# Inverter_V2.net
KiCad netlist of a schematic drawn in EAGLE
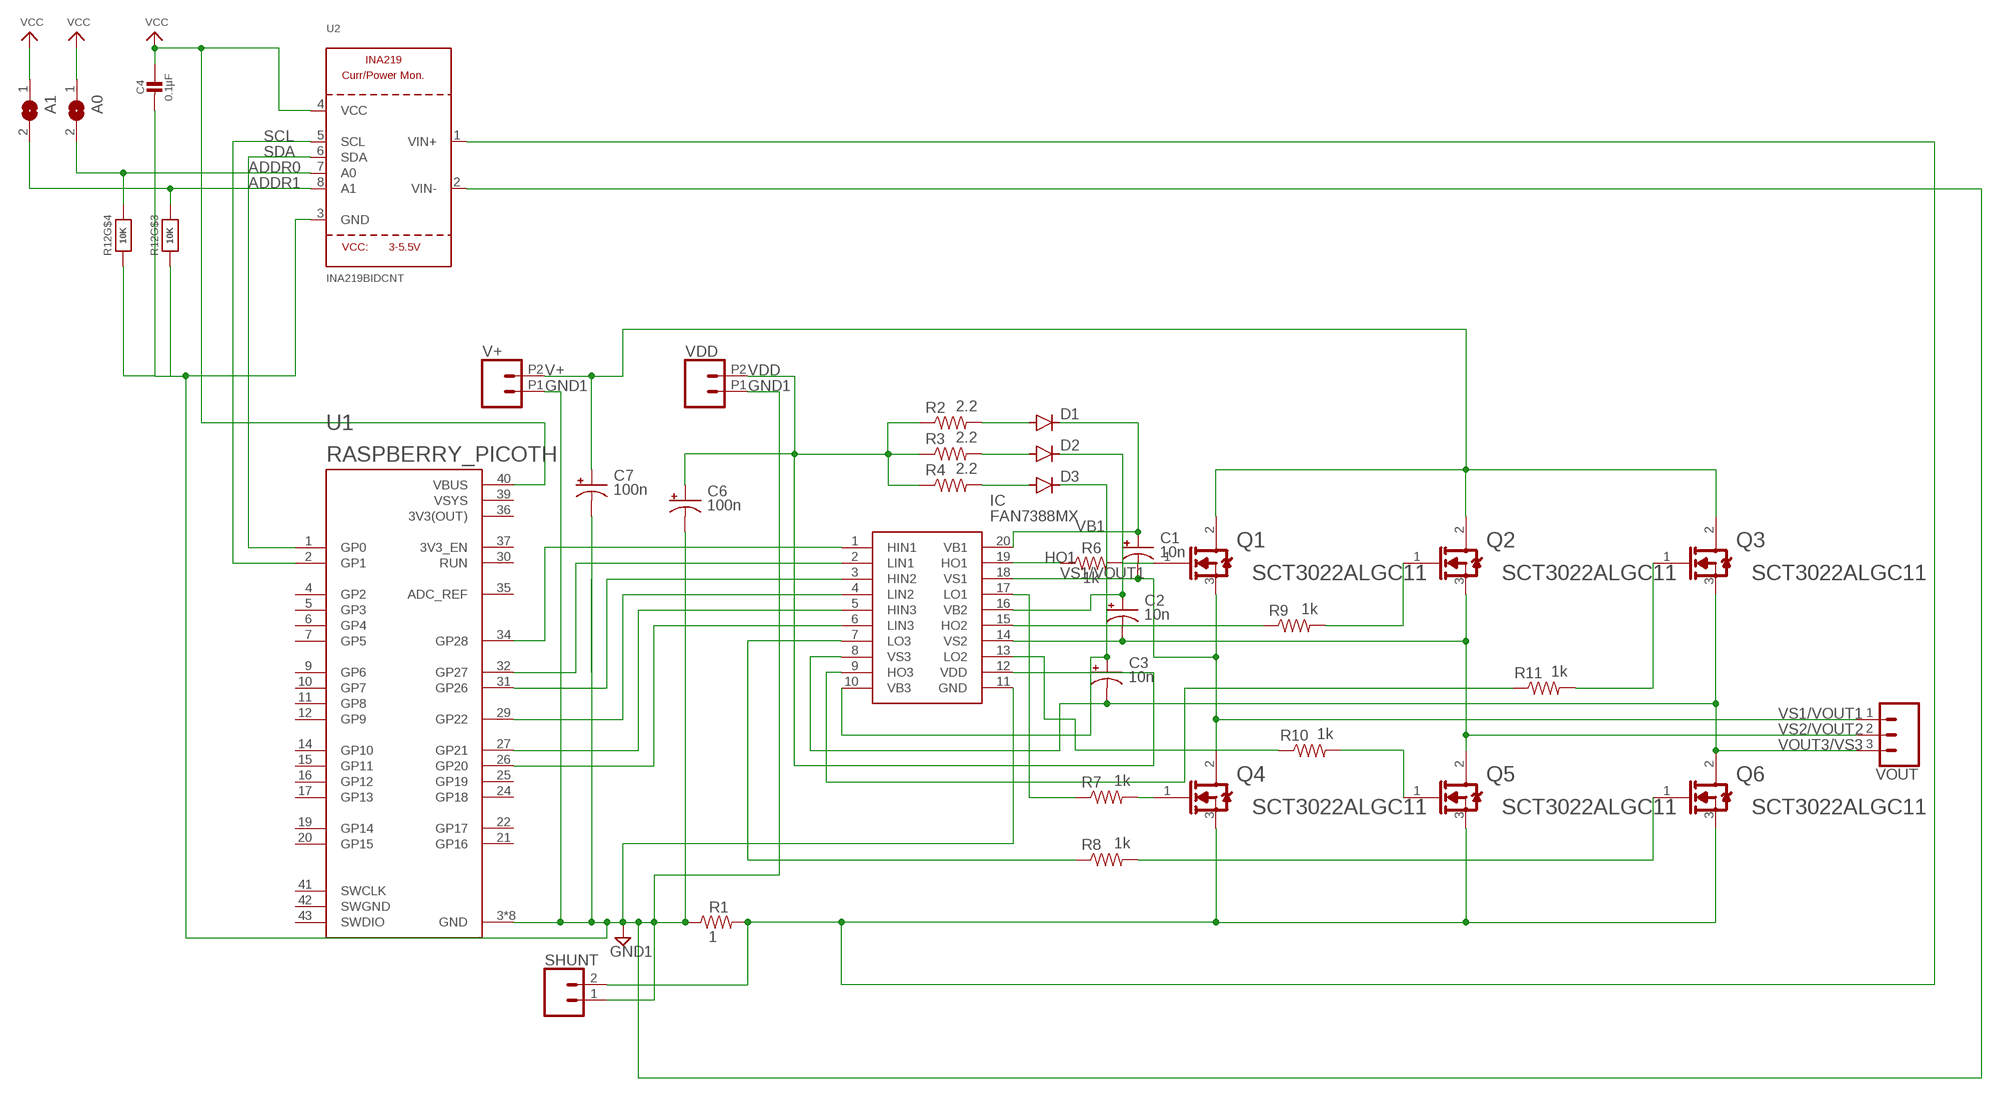
[diagram p0: schematic, sheet 1]

(export (version "E")
  (design (tool "Eeschema 10.0.6"))
  (components
    (comp (ref "A0")
      (value "SOLDERJUMPERREFLOW_NOPASTE")
      (footprint "eagle-import:SOLDERJUMPER_REFLOW_NOPASTE")
      (libsource (lib "eagle-import") (part "SOLDERJUMPERREFLOW_NOPASTE"))
    )
    (comp (ref "A1")
      (value "SOLDERJUMPERREFLOW_NOPASTE")
      (footprint "eagle-import:SOLDERJUMPER_REFLOW_NOPASTE")
      (libsource (lib "eagle-import") (part "SOLDERJUMPERREFLOW_NOPASTE"))
    )
    (comp (ref "C1")
      (value "10n")
      (footprint "eagle-import:SMC_Z")
      (libsource (lib "eagle-import") (part "CPOL-USSMCZ"))
    )
    (comp (ref "C2")
      (value "10n")
      (footprint "eagle-import:SMC_Z")
      (libsource (lib "eagle-import") (part "CPOL-USSMCZ"))
    )
    (comp (ref "C3")
      (value "10n")
      (footprint "eagle-import:SMC_Z")
      (libsource (lib "eagle-import") (part "CPOL-USSMCZ"))
    )
    (comp (ref "C4")
      (value "0.1µF")
      (footprint "eagle-import:0603-NO")
      (libsource (lib "eagle-import") (part "CAP_CERAMIC0603_NO"))
    )
    (comp (ref "C6")
      (value "100n")
      (footprint "eagle-import:SMC_Z")
      (libsource (lib "eagle-import") (part "CPOL-USSMCZ"))
    )
    (comp (ref "C7")
      (value "100n")
      (footprint "eagle-import:E5-5")
      (libsource (lib "eagle-import") (part "CPOL-USE5-5"))
    )
    (comp (ref "D1")
      (value "DIODE-GF1")
      (footprint "eagle-import:GF1")
      (libsource (lib "eagle-import") (part "DIODE-GF1"))
    )
    (comp (ref "D2")
      (value "DIODE-GF1")
      (footprint "eagle-import:GF1")
      (libsource (lib "eagle-import") (part "DIODE-GF1"))
    )
    (comp (ref "D3")
      (value "DIODE-GF1")
      (footprint "eagle-import:GF1")
      (libsource (lib "eagle-import") (part "DIODE-GF1"))
    )
    (comp (ref "IC")
      (value "FAN7388MX")
      (footprint "eagle-import:SOIC127P1032X265-20N")
      (fields (field (name "MOUSER_PART_NUMBER") "512-FAN7388MX"))
      (libsource (lib "eagle-import") (part "FAN7388MX"))
    )
    (comp (ref "Q1")
      (value "ROHM_SCT3022ALGC11ROHM_SCT3022ALGC11_0_0")
      (footprint "eagle-import:ROHM_SCT3022ALGC11_0")
      (fields
        (field (name "DIGIKEY_PART_NUMBER") "SCT3022ALGC11-ND")
        (field (name "MF") "ROHM")
        (field (name "MOUSER_PART_NUMBER") "755-SCT3022ALGC11")
      )
      (libsource (lib "eagle-import") (part "ROHM_SCT3022ALGC11ROHM_SCT3022ALGC11_0_0"))
    )
    (comp (ref "Q2")
      (value "ROHM_SCT3022ALGC11ROHM_SCT3022ALGC11_0_0")
      (footprint "eagle-import:ROHM_SCT3022ALGC11_0")
      (fields
        (field (name "DIGIKEY_PART_NUMBER") "SCT3022ALGC11-ND")
        (field (name "MF") "ROHM")
        (field (name "MOUSER_PART_NUMBER") "755-SCT3022ALGC11")
      )
      (libsource (lib "eagle-import") (part "ROHM_SCT3022ALGC11ROHM_SCT3022ALGC11_0_0"))
    )
    (comp (ref "Q3")
      (value "ROHM_SCT3022ALGC11ROHM_SCT3022ALGC11_0_0")
      (footprint "eagle-import:ROHM_SCT3022ALGC11_0")
      (fields
        (field (name "DIGIKEY_PART_NUMBER") "SCT3022ALGC11-ND")
        (field (name "MF") "ROHM")
        (field (name "MOUSER_PART_NUMBER") "755-SCT3022ALGC11")
      )
      (libsource (lib "eagle-import") (part "ROHM_SCT3022ALGC11ROHM_SCT3022ALGC11_0_0"))
    )
    (comp (ref "Q4")
      (value "ROHM_SCT3022ALGC11ROHM_SCT3022ALGC11_0_0")
      (footprint "eagle-import:ROHM_SCT3022ALGC11_0")
      (fields
        (field (name "DIGIKEY_PART_NUMBER") "SCT3022ALGC11-ND")
        (field (name "MF") "ROHM")
        (field (name "MOUSER_PART_NUMBER") "755-SCT3022ALGC11")
      )
      (libsource (lib "eagle-import") (part "ROHM_SCT3022ALGC11ROHM_SCT3022ALGC11_0_0"))
    )
    (comp (ref "Q5")
      (value "ROHM_SCT3022ALGC11ROHM_SCT3022ALGC11_0_0")
      (footprint "eagle-import:ROHM_SCT3022ALGC11_0")
      (fields
        (field (name "DIGIKEY_PART_NUMBER") "SCT3022ALGC11-ND")
        (field (name "MF") "ROHM")
        (field (name "MOUSER_PART_NUMBER") "755-SCT3022ALGC11")
      )
      (libsource (lib "eagle-import") (part "ROHM_SCT3022ALGC11ROHM_SCT3022ALGC11_0_0"))
    )
    (comp (ref "Q6")
      (value "ROHM_SCT3022ALGC11ROHM_SCT3022ALGC11_0_0")
      (footprint "eagle-import:ROHM_SCT3022ALGC11_0")
      (fields
        (field (name "DIGIKEY_PART_NUMBER") "SCT3022ALGC11-ND")
        (field (name "MF") "ROHM")
        (field (name "MOUSER_PART_NUMBER") "755-SCT3022ALGC11")
      )
      (libsource (lib "eagle-import") (part "ROHM_SCT3022ALGC11ROHM_SCT3022ALGC11_0_0"))
    )
    (comp (ref "R1")
      (value "1")
      (footprint "eagle-import:0207_10")
      (libsource (lib "eagle-import") (part "R-US_0207/10"))
    )
    (comp (ref "R2")
      (value "2.2")
      (footprint "eagle-import:0603")
      (libsource (lib "eagle-import") (part "RESISTOR0603"))
    )
    (comp (ref "R3")
      (value "2.2")
      (footprint "eagle-import:0603")
      (libsource (lib "eagle-import") (part "RESISTOR0603"))
    )
    (comp (ref "R4")
      (value "2.2")
      (footprint "eagle-import:0603")
      (libsource (lib "eagle-import") (part "RESISTOR0603"))
    )
    (comp (ref "R6")
      (value "1k")
      (footprint "eagle-import:0603")
      (libsource (lib "eagle-import") (part "RESISTOR0603"))
    )
    (comp (ref "R7")
      (value "1k")
      (footprint "eagle-import:0603")
      (libsource (lib "eagle-import") (part "RESISTOR0603"))
    )
    (comp (ref "R8")
      (value "1k")
      (footprint "eagle-import:0603")
      (libsource (lib "eagle-import") (part "RESISTOR0603"))
    )
    (comp (ref "R9")
      (value "1k")
      (footprint "eagle-import:0603")
      (libsource (lib "eagle-import") (part "RESISTOR0603"))
    )
    (comp (ref "R10")
      (value "1k")
      (footprint "eagle-import:0603")
      (libsource (lib "eagle-import") (part "RESISTOR0603"))
    )
    (comp (ref "R11")
      (value "1k")
      (footprint "eagle-import:0603")
      (libsource (lib "eagle-import") (part "RESISTOR0603"))
    )
    (comp (ref "R12")
      (value "10K")
      (footprint "eagle-import:RESPACK_4X0603")
      (libsource (lib "eagle-import") (part "RESISTOR_4PACK"))
    )
    (comp (ref "SHUNT")
      (value "CONN_02PTH4")
      (footprint "eagle-import:1X02_XTRA_BIG")
      (libsource (lib "eagle-import") (part "CONN_02PTH4"))
    )
    (comp (ref "U1")
      (value "RASPBERRY_PICOTH")
      (footprint "eagle-import:PICO-PKG-TH")
      (libsource (lib "eagle-import") (part "RASPBERRY_PICOTH"))
    )
    (comp (ref "U2")
      (value "INA219BIDCNT")
      (footprint "eagle-import:SOT23-8")
      (libsource (lib "eagle-import") (part "INA219"))
    )
    (comp (ref "V+")
      (value "CONN_022.54MM_SCREWTERM")
      (footprint "eagle-import:1X02_2.54_SCREWTERM")
      (libsource (lib "eagle-import") (part "CONN_022.54MM_SCREWTERM"))
    )
    (comp (ref "VDD")
      (value "CONN_022.54MM_SCREWTERM")
      (footprint "eagle-import:1X02_2.54_SCREWTERM")
      (libsource (lib "eagle-import") (part "CONN_022.54MM_SCREWTERM"))
    )
    (comp (ref "VOUT")
      (value "CONN_03SCREW-NS")
      (footprint "eagle-import:SCREWTERMINAL-3.5MM-3-NS")
      (libsource (lib "eagle-import") (part "CONN_03SCREW-NS"))
    )
  )
  (nets
    (net (code "1") (name "/3V3(OUT)") (class "Default")
      (node (ref "U1") (pin "36") (pinfunction "3V3(OUT)_36") (pintype "power_in"))
    )
    (net (code "2") (name "/ADDR0") (class "Default")
      (node (ref "A0") (pin "2") (pinfunction "2_2") (pintype "passive"))
      (node (ref "R12") (pin "5") (pinfunction "2_5") (pintype "passive"))
      (node (ref "U2") (pin "7") (pinfunction "A0_7") (pintype "bidirectional"))
    )
    (net (code "3") (name "/ADDR1") (class "Default")
      (node (ref "A1") (pin "2") (pinfunction "2_2") (pintype "passive"))
      (node (ref "R12") (pin "6") (pinfunction "2_6") (pintype "passive"))
      (node (ref "U2") (pin "8") (pinfunction "A1_8") (pintype "bidirectional"))
    )
    (net (code "4") (name "/HO1") (class "Default")
      (node (ref "IC") (pin "19") (pinfunction "HO1_19") (pintype "bidirectional"))
      (node (ref "R6") (pin "1") (pinfunction "1_1") (pintype "passive"))
    )
    (net (code "5") (name "/SCL") (class "Default")
      (node (ref "U1") (pin "2") (pinfunction "GP1_2") (pintype "bidirectional"))
      (node (ref "U2") (pin "5") (pinfunction "SCL_5") (pintype "bidirectional"))
    )
    (net (code "6") (name "/SDA") (class "Default")
      (node (ref "U1") (pin "1") (pinfunction "GP0_1") (pintype "bidirectional"))
      (node (ref "U2") (pin "6") (pinfunction "SDA_6") (pintype "bidirectional"))
    )
    (net (code "7") (name "/SWGND") (class "Default")
      (node (ref "U1") (pin "42") (pinfunction "SWGND_42") (pintype "power_in"))
    )
    (net (code "8") (name "/V+") (class "Default")
      (node (ref "C7") (pin "+") (pinfunction "+_+") (pintype "passive"))
      (node (ref "Q1") (pin "2") (pinfunction "DRAIN_2") (pintype "passive"))
      (node (ref "Q2") (pin "2") (pinfunction "DRAIN_2") (pintype "passive"))
      (node (ref "Q3") (pin "2") (pinfunction "DRAIN_2") (pintype "passive"))
      (node (ref "V+") (pin "P2") (pinfunction "2_P2") (pintype "passive"))
    )
    (net (code "9") (name "/VB1") (class "Default")
      (node (ref "C1") (pin "+") (pinfunction "+_+") (pintype "passive"))
      (node (ref "D1") (pin "C") (pinfunction "C_C") (pintype "passive"))
      (node (ref "IC") (pin "20") (pinfunction "VB1_20") (pintype "bidirectional"))
    )
    (net (code "10") (name "/VDD") (class "Default")
      (node (ref "C6") (pin "+") (pinfunction "+_+") (pintype "passive"))
      (node (ref "IC") (pin "12") (pinfunction "VDD_12") (pintype "bidirectional"))
      (node (ref "R2") (pin "1") (pinfunction "1_1") (pintype "passive"))
      (node (ref "R3") (pin "1") (pinfunction "1_1") (pintype "passive"))
      (node (ref "R4") (pin "1") (pinfunction "1_1") (pintype "passive"))
      (node (ref "VDD") (pin "P2") (pinfunction "2_P2") (pintype "passive"))
    )
    (net (code "11") (name "/VOUT3{slash}VS3") (class "Default")
      (node (ref "C3") (pin "-") (pinfunction "-_-") (pintype "passive"))
      (node (ref "IC") (pin "8") (pinfunction "VS3_8") (pintype "bidirectional"))
      (node (ref "Q3") (pin "3") (pinfunction "SOURCE_3") (pintype "passive"))
      (node (ref "Q6") (pin "2") (pinfunction "DRAIN_2") (pintype "passive"))
      (node (ref "VOUT") (pin "3") (pinfunction "3_3") (pintype "passive"))
    )
    (net (code "12") (name "/VS1{slash}VOUT1") (class "Default")
      (node (ref "C1") (pin "-") (pinfunction "-_-") (pintype "passive"))
      (node (ref "IC") (pin "18") (pinfunction "VS1_18") (pintype "bidirectional"))
      (node (ref "Q1") (pin "3") (pinfunction "SOURCE_3") (pintype "passive"))
      (node (ref "Q4") (pin "2") (pinfunction "DRAIN_2") (pintype "passive"))
      (node (ref "VOUT") (pin "1") (pinfunction "1_1") (pintype "passive"))
    )
    (net (code "13") (name "/VS2{slash}VOUT2") (class "Default")
      (node (ref "C2") (pin "-") (pinfunction "-_-") (pintype "passive"))
      (node (ref "IC") (pin "14") (pinfunction "VS2_14") (pintype "bidirectional"))
      (node (ref "Q2") (pin "3") (pinfunction "SOURCE_3") (pintype "passive"))
      (node (ref "Q5") (pin "2") (pinfunction "DRAIN_2") (pintype "passive"))
      (node (ref "VOUT") (pin "2") (pinfunction "2_2") (pintype "passive"))
    )
    (net (code "14") (name "/VSYS") (class "Default")
      (node (ref "U1") (pin "39") (pinfunction "VSYS_39") (pintype "power_in"))
    )
    (net (code "15") (name "GND1") (class "Default")
      (node (ref "C4") (pin "2") (pinfunction "2_2") (pintype "passive"))
      (node (ref "C6") (pin "-") (pinfunction "-_-") (pintype "passive"))
      (node (ref "C7") (pin "-") (pinfunction "-_-") (pintype "passive"))
      (node (ref "IC") (pin "11") (pinfunction "GND_11") (pintype "bidirectional"))
      (node (ref "R1") (pin "1") (pinfunction "1_1") (pintype "passive"))
      (node (ref "R12") (pin "3") (pinfunction "1_3") (pintype "passive"))
      (node (ref "R12") (pin "4") (pinfunction "1_4") (pintype "passive"))
      (node (ref "SHUNT") (pin "1") (pinfunction "1_1") (pintype "passive"))
      (node (ref "U1") (pin "13") (pinfunction "GND_13") (pintype "power_in"))
      (node (ref "U1") (pin "18") (pinfunction "GND_18") (pintype "power_in"))
      (node (ref "U1") (pin "23") (pinfunction "GND_23") (pintype "power_in"))
      (node (ref "U1") (pin "28") (pinfunction "GND_28") (pintype "power_in"))
      (node (ref "U1") (pin "3") (pinfunction "GND_3") (pintype "power_in"))
      (node (ref "U1") (pin "33") (pinfunction "GND_33") (pintype "power_in"))
      (node (ref "U1") (pin "38") (pinfunction "GND_38") (pintype "power_in"))
      (node (ref "U1") (pin "8") (pinfunction "GND_8") (pintype "power_in"))
      (node (ref "U2") (pin "2") (pinfunction "VIN-_2") (pintype "bidirectional"))
      (node (ref "U2") (pin "3") (pinfunction "GND_3") (pintype "power_in"))
      (node (ref "V+") (pin "P1") (pinfunction "1_P1") (pintype "passive"))
      (node (ref "VDD") (pin "P1") (pinfunction "1_P1") (pintype "passive"))
    )
    (net (code "16") (name "Net-(D1-PadA)") (class "Default")
      (node (ref "D1") (pin "A") (pinfunction "A_A") (pintype "passive"))
      (node (ref "R2") (pin "2") (pinfunction "2_2") (pintype "passive"))
    )
    (net (code "17") (name "Net-(D2-PadA)") (class "Default")
      (node (ref "D2") (pin "A") (pinfunction "A_A") (pintype "passive"))
      (node (ref "R3") (pin "2") (pinfunction "2_2") (pintype "passive"))
    )
    (net (code "18") (name "Net-(D3-PadA)") (class "Default")
      (node (ref "D3") (pin "A") (pinfunction "A_A") (pintype "passive"))
      (node (ref "R4") (pin "2") (pinfunction "2_2") (pintype "passive"))
    )
    (net (code "19") (name "Net-(IC-HIN1)") (class "Default")
      (node (ref "IC") (pin "1") (pinfunction "HIN1_1") (pintype "bidirectional"))
      (node (ref "U1") (pin "34") (pinfunction "GP28_34") (pintype "bidirectional"))
    )
    (net (code "20") (name "Net-(IC-HIN2)") (class "Default")
      (node (ref "IC") (pin "3") (pinfunction "HIN2_3") (pintype "bidirectional"))
      (node (ref "U1") (pin "31") (pinfunction "GP26_31") (pintype "bidirectional"))
    )
    (net (code "21") (name "Net-(IC-HIN3)") (class "Default")
      (node (ref "IC") (pin "5") (pinfunction "HIN3_5") (pintype "bidirectional"))
      (node (ref "U1") (pin "27") (pinfunction "GP21_27") (pintype "bidirectional"))
    )
    (net (code "22") (name "Net-(IC-HO2)") (class "Default")
      (node (ref "IC") (pin "15") (pinfunction "HO2_15") (pintype "bidirectional"))
      (node (ref "R9") (pin "1") (pinfunction "1_1") (pintype "passive"))
    )
    (net (code "23") (name "Net-(IC-HO3)") (class "Default")
      (node (ref "IC") (pin "9") (pinfunction "HO3_9") (pintype "bidirectional"))
      (node (ref "R11") (pin "1") (pinfunction "1_1") (pintype "passive"))
    )
    (net (code "24") (name "Net-(IC-LIN1)") (class "Default")
      (node (ref "IC") (pin "2") (pinfunction "LIN1_2") (pintype "bidirectional"))
      (node (ref "U1") (pin "32") (pinfunction "GP27_32") (pintype "bidirectional"))
    )
    (net (code "25") (name "Net-(IC-LIN2)") (class "Default")
      (node (ref "IC") (pin "4") (pinfunction "LIN2_4") (pintype "bidirectional"))
      (node (ref "U1") (pin "29") (pinfunction "GP22_29") (pintype "bidirectional"))
    )
    (net (code "26") (name "Net-(IC-LIN3)") (class "Default")
      (node (ref "IC") (pin "6") (pinfunction "LIN3_6") (pintype "bidirectional"))
      (node (ref "U1") (pin "26") (pinfunction "GP20_26") (pintype "bidirectional"))
    )
    (net (code "27") (name "Net-(IC-LO1)") (class "Default")
      (node (ref "IC") (pin "17") (pinfunction "LO1_17") (pintype "bidirectional"))
      (node (ref "R7") (pin "1") (pinfunction "1_1") (pintype "passive"))
    )
    (net (code "28") (name "Net-(IC-LO2)") (class "Default")
      (node (ref "IC") (pin "13") (pinfunction "LO2_13") (pintype "bidirectional"))
      (node (ref "R10") (pin "1") (pinfunction "1_1") (pintype "passive"))
    )
    (net (code "29") (name "Net-(IC-LO3)") (class "Default")
      (node (ref "IC") (pin "7") (pinfunction "LO3_7") (pintype "bidirectional"))
      (node (ref "R8") (pin "1") (pinfunction "1_1") (pintype "passive"))
    )
    (net (code "30") (name "Net-(IC-VB2)") (class "Default")
      (node (ref "C2") (pin "+") (pinfunction "+_+") (pintype "passive"))
      (node (ref "D2") (pin "C") (pinfunction "C_C") (pintype "passive"))
      (node (ref "IC") (pin "16") (pinfunction "VB2_16") (pintype "bidirectional"))
    )
    (net (code "31") (name "Net-(IC-VB3)") (class "Default")
      (node (ref "C3") (pin "+") (pinfunction "+_+") (pintype "passive"))
      (node (ref "D3") (pin "C") (pinfunction "C_C") (pintype "passive"))
      (node (ref "IC") (pin "10") (pinfunction "VB3_10") (pintype "bidirectional"))
    )
    (net (code "32") (name "Net-(Q1-GATE)") (class "Default")
      (node (ref "Q1") (pin "1") (pinfunction "GATE_1") (pintype "passive"))
      (node (ref "R6") (pin "2") (pinfunction "2_2") (pintype "passive"))
    )
    (net (code "33") (name "Net-(Q2-GATE)") (class "Default")
      (node (ref "Q2") (pin "1") (pinfunction "GATE_1") (pintype "passive"))
      (node (ref "R9") (pin "2") (pinfunction "2_2") (pintype "passive"))
    )
    (net (code "34") (name "Net-(Q3-GATE)") (class "Default")
      (node (ref "Q3") (pin "1") (pinfunction "GATE_1") (pintype "passive"))
      (node (ref "R11") (pin "2") (pinfunction "2_2") (pintype "passive"))
    )
    (net (code "35") (name "Net-(Q4-GATE)") (class "Default")
      (node (ref "Q4") (pin "1") (pinfunction "GATE_1") (pintype "passive"))
      (node (ref "R7") (pin "2") (pinfunction "2_2") (pintype "passive"))
    )
    (net (code "36") (name "Net-(Q4-SOURCE)") (class "Default")
      (node (ref "Q4") (pin "3") (pinfunction "SOURCE_3") (pintype "passive"))
      (node (ref "Q5") (pin "3") (pinfunction "SOURCE_3") (pintype "passive"))
      (node (ref "Q6") (pin "3") (pinfunction "SOURCE_3") (pintype "passive"))
      (node (ref "R1") (pin "2") (pinfunction "2_2") (pintype "passive"))
      (node (ref "SHUNT") (pin "2") (pinfunction "2_2") (pintype "passive"))
      (node (ref "U2") (pin "1") (pinfunction "VIN+_1") (pintype "bidirectional"))
    )
    (net (code "37") (name "Net-(Q5-GATE)") (class "Default")
      (node (ref "Q5") (pin "1") (pinfunction "GATE_1") (pintype "passive"))
      (node (ref "R10") (pin "2") (pinfunction "2_2") (pintype "passive"))
    )
    (net (code "38") (name "Net-(Q6-GATE)") (class "Default")
      (node (ref "Q6") (pin "1") (pinfunction "GATE_1") (pintype "passive"))
      (node (ref "R8") (pin "2") (pinfunction "2_2") (pintype "passive"))
    )
    (net (code "39") (name "VCC") (class "Default")
      (node (ref "A0") (pin "1") (pinfunction "1_1") (pintype "passive"))
      (node (ref "A1") (pin "1") (pinfunction "1_1") (pintype "passive"))
      (node (ref "C4") (pin "1") (pinfunction "1_1") (pintype "passive"))
      (node (ref "U1") (pin "40") (pinfunction "VBUS_40") (pintype "power_in"))
      (node (ref "U2") (pin "4") (pinfunction "VCC_4") (pintype "power_in"))
    )
    (net (code "40") (name "unconnected-(U1-3V3_EN-Pad37)") (class "Default")
      (node (ref "U1") (pin "37") (pinfunction "3V3_EN_37") (pintype "input"))
    )
    (net (code "41") (name "unconnected-(U1-ADC_REF-Pad35)") (class "Default")
      (node (ref "U1") (pin "35") (pinfunction "ADC_REF_35") (pintype "input"))
    )
    (net (code "42") (name "unconnected-(U1-GP2-Pad4)") (class "Default")
      (node (ref "U1") (pin "4") (pinfunction "GP2_4") (pintype "bidirectional"))
    )
    (net (code "43") (name "unconnected-(U1-GP3-Pad5)") (class "Default")
      (node (ref "U1") (pin "5") (pinfunction "GP3_5") (pintype "bidirectional"))
    )
    (net (code "44") (name "unconnected-(U1-GP4-Pad6)") (class "Default")
      (node (ref "U1") (pin "6") (pinfunction "GP4_6") (pintype "bidirectional"))
    )
    (net (code "45") (name "unconnected-(U1-GP5-Pad7)") (class "Default")
      (node (ref "U1") (pin "7") (pinfunction "GP5_7") (pintype "bidirectional"))
    )
    (net (code "46") (name "unconnected-(U1-GP6-Pad9)") (class "Default")
      (node (ref "U1") (pin "9") (pinfunction "GP6_9") (pintype "bidirectional"))
    )
    (net (code "47") (name "unconnected-(U1-GP7-Pad10)") (class "Default")
      (node (ref "U1") (pin "10") (pinfunction "GP7_10") (pintype "bidirectional"))
    )
    (net (code "48") (name "unconnected-(U1-GP8-Pad11)") (class "Default")
      (node (ref "U1") (pin "11") (pinfunction "GP8_11") (pintype "bidirectional"))
    )
    (net (code "49") (name "unconnected-(U1-GP9-Pad12)") (class "Default")
      (node (ref "U1") (pin "12") (pinfunction "GP9_12") (pintype "bidirectional"))
    )
    (net (code "50") (name "unconnected-(U1-GP10-Pad14)") (class "Default")
      (node (ref "U1") (pin "14") (pinfunction "GP10_14") (pintype "bidirectional"))
    )
    (net (code "51") (name "unconnected-(U1-GP11-Pad15)") (class "Default")
      (node (ref "U1") (pin "15") (pinfunction "GP11_15") (pintype "bidirectional"))
    )
    (net (code "52") (name "unconnected-(U1-GP12-Pad16)") (class "Default")
      (node (ref "U1") (pin "16") (pinfunction "GP12_16") (pintype "bidirectional"))
    )
    (net (code "53") (name "unconnected-(U1-GP13-Pad17)") (class "Default")
      (node (ref "U1") (pin "17") (pinfunction "GP13_17") (pintype "bidirectional"))
    )
    (net (code "54") (name "unconnected-(U1-GP14-Pad19)") (class "Default")
      (node (ref "U1") (pin "19") (pinfunction "GP14_19") (pintype "bidirectional"))
    )
    (net (code "55") (name "unconnected-(U1-GP15-Pad20)") (class "Default")
      (node (ref "U1") (pin "20") (pinfunction "GP15_20") (pintype "bidirectional"))
    )
    (net (code "56") (name "unconnected-(U1-GP16-Pad21)") (class "Default")
      (node (ref "U1") (pin "21") (pinfunction "GP16_21") (pintype "bidirectional"))
    )
    (net (code "57") (name "unconnected-(U1-GP17-Pad22)") (class "Default")
      (node (ref "U1") (pin "22") (pinfunction "GP17_22") (pintype "bidirectional"))
    )
    (net (code "58") (name "unconnected-(U1-GP18-Pad24)") (class "Default")
      (node (ref "U1") (pin "24") (pinfunction "GP18_24") (pintype "bidirectional"))
    )
    (net (code "59") (name "unconnected-(U1-GP19-Pad25)") (class "Default")
      (node (ref "U1") (pin "25") (pinfunction "GP19_25") (pintype "bidirectional"))
    )
    (net (code "60") (name "unconnected-(U1-RUN-Pad30)") (class "Default")
      (node (ref "U1") (pin "30") (pinfunction "RUN_30") (pintype "input"))
    )
    (net (code "61") (name "unconnected-(U1-SWCLK-Pad41)") (class "Default")
      (node (ref "U1") (pin "41") (pinfunction "SWCLK_41") (pintype "input"))
    )
    (net (code "62") (name "unconnected-(U1-SWDIO-Pad43)") (class "Default")
      (node (ref "U1") (pin "43") (pinfunction "SWDIO_43") (pintype "bidirectional"))
    )
  )
)
